# block_udn2951Z.net
KiCad netlist of a schematic drawn in EAGLE
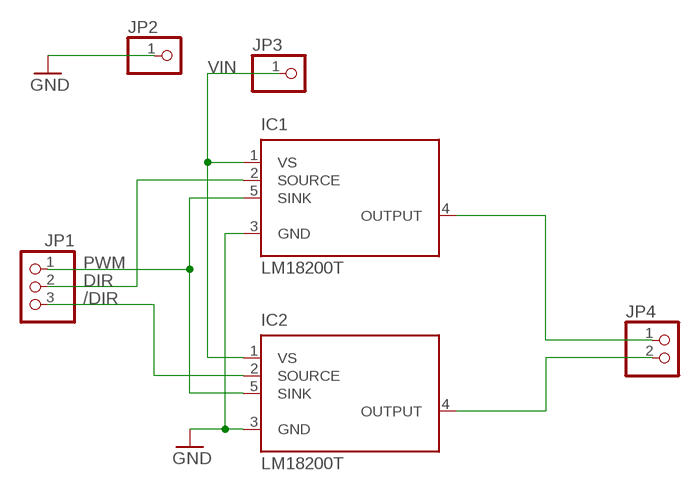
[diagram p0: schematic, sheet 1]

(export (version "E")
  (design (tool "Eeschema 10.0.6"))
  (components
    (comp (ref "IC1")
      (value "LM18200T")
      (footprint "eagle-import:T05A")
      (libsource (lib "eagle-import") (part "LM18200T"))
    )
    (comp (ref "IC2")
      (value "LM18200T")
      (footprint "eagle-import:T05A")
      (libsource (lib "eagle-import") (part "LM18200T"))
    )
    (comp (ref "JP1")
      (value "PINHD-1X3")
      (footprint "eagle-import:1X03")
      (libsource (lib "eagle-import") (part "PINHD-1X3"))
    )
    (comp (ref "JP2")
      (value "PINHD-1X1")
      (footprint "eagle-import:1X01")
      (libsource (lib "eagle-import") (part "PINHD-1X1"))
    )
    (comp (ref "JP3")
      (value "PINHD-1X1")
      (footprint "eagle-import:1X01")
      (libsource (lib "eagle-import") (part "PINHD-1X1"))
    )
    (comp (ref "JP4")
      (value "PINHD-1X2")
      (footprint "eagle-import:1X02")
      (libsource (lib "eagle-import") (part "PINHD-1X2"))
    )
  )
  (nets
    (net (code "1") (name "/DIR") (class "Default")
      (node (ref "IC1") (pin "2") (pinfunction "SOURCE_2") (pintype "input"))
      (node (ref "JP1") (pin "2") (pinfunction "2_2") (pintype "passive"))
    )
    (net (code "2") (name "/PWM") (class "Default")
      (node (ref "IC1") (pin "5") (pinfunction "SINK_5") (pintype "input"))
      (node (ref "IC2") (pin "5") (pinfunction "SINK_5") (pintype "input"))
      (node (ref "JP1") (pin "1") (pinfunction "1_1") (pintype "passive"))
    )
    (net (code "3") (name "/VIN") (class "Default")
      (node (ref "IC1") (pin "1") (pinfunction "VS_1") (pintype "power_in"))
      (node (ref "IC2") (pin "1") (pinfunction "VS_1") (pintype "power_in"))
      (node (ref "JP3") (pin "1") (pinfunction "1_1") (pintype "passive"))
    )
    (net (code "4") (name "/{slash}DIR") (class "Default")
      (node (ref "IC2") (pin "2") (pinfunction "SOURCE_2") (pintype "input"))
      (node (ref "JP1") (pin "3") (pinfunction "3_3") (pintype "passive"))
    )
    (net (code "5") (name "GND") (class "Default")
      (node (ref "IC1") (pin "3") (pinfunction "GND_3") (pintype "power_in"))
      (node (ref "IC2") (pin "3") (pinfunction "GND_3") (pintype "power_in"))
      (node (ref "JP2") (pin "1") (pinfunction "1_1") (pintype "passive"))
    )
    (net (code "6") (name "Net-(IC1-OUTPUT)") (class "Default")
      (node (ref "IC1") (pin "4") (pinfunction "OUTPUT_4") (pintype "output"))
      (node (ref "JP4") (pin "1") (pinfunction "1_1") (pintype "passive"))
    )
    (net (code "7") (name "Net-(IC2-OUTPUT)") (class "Default")
      (node (ref "IC2") (pin "4") (pinfunction "OUTPUT_4") (pintype "output"))
      (node (ref "JP4") (pin "2") (pinfunction "2_2") (pintype "passive"))
    )
  )
)
